# USB_PowerOnly.net
KiCad netlist of a schematic drawn in Altium Designer
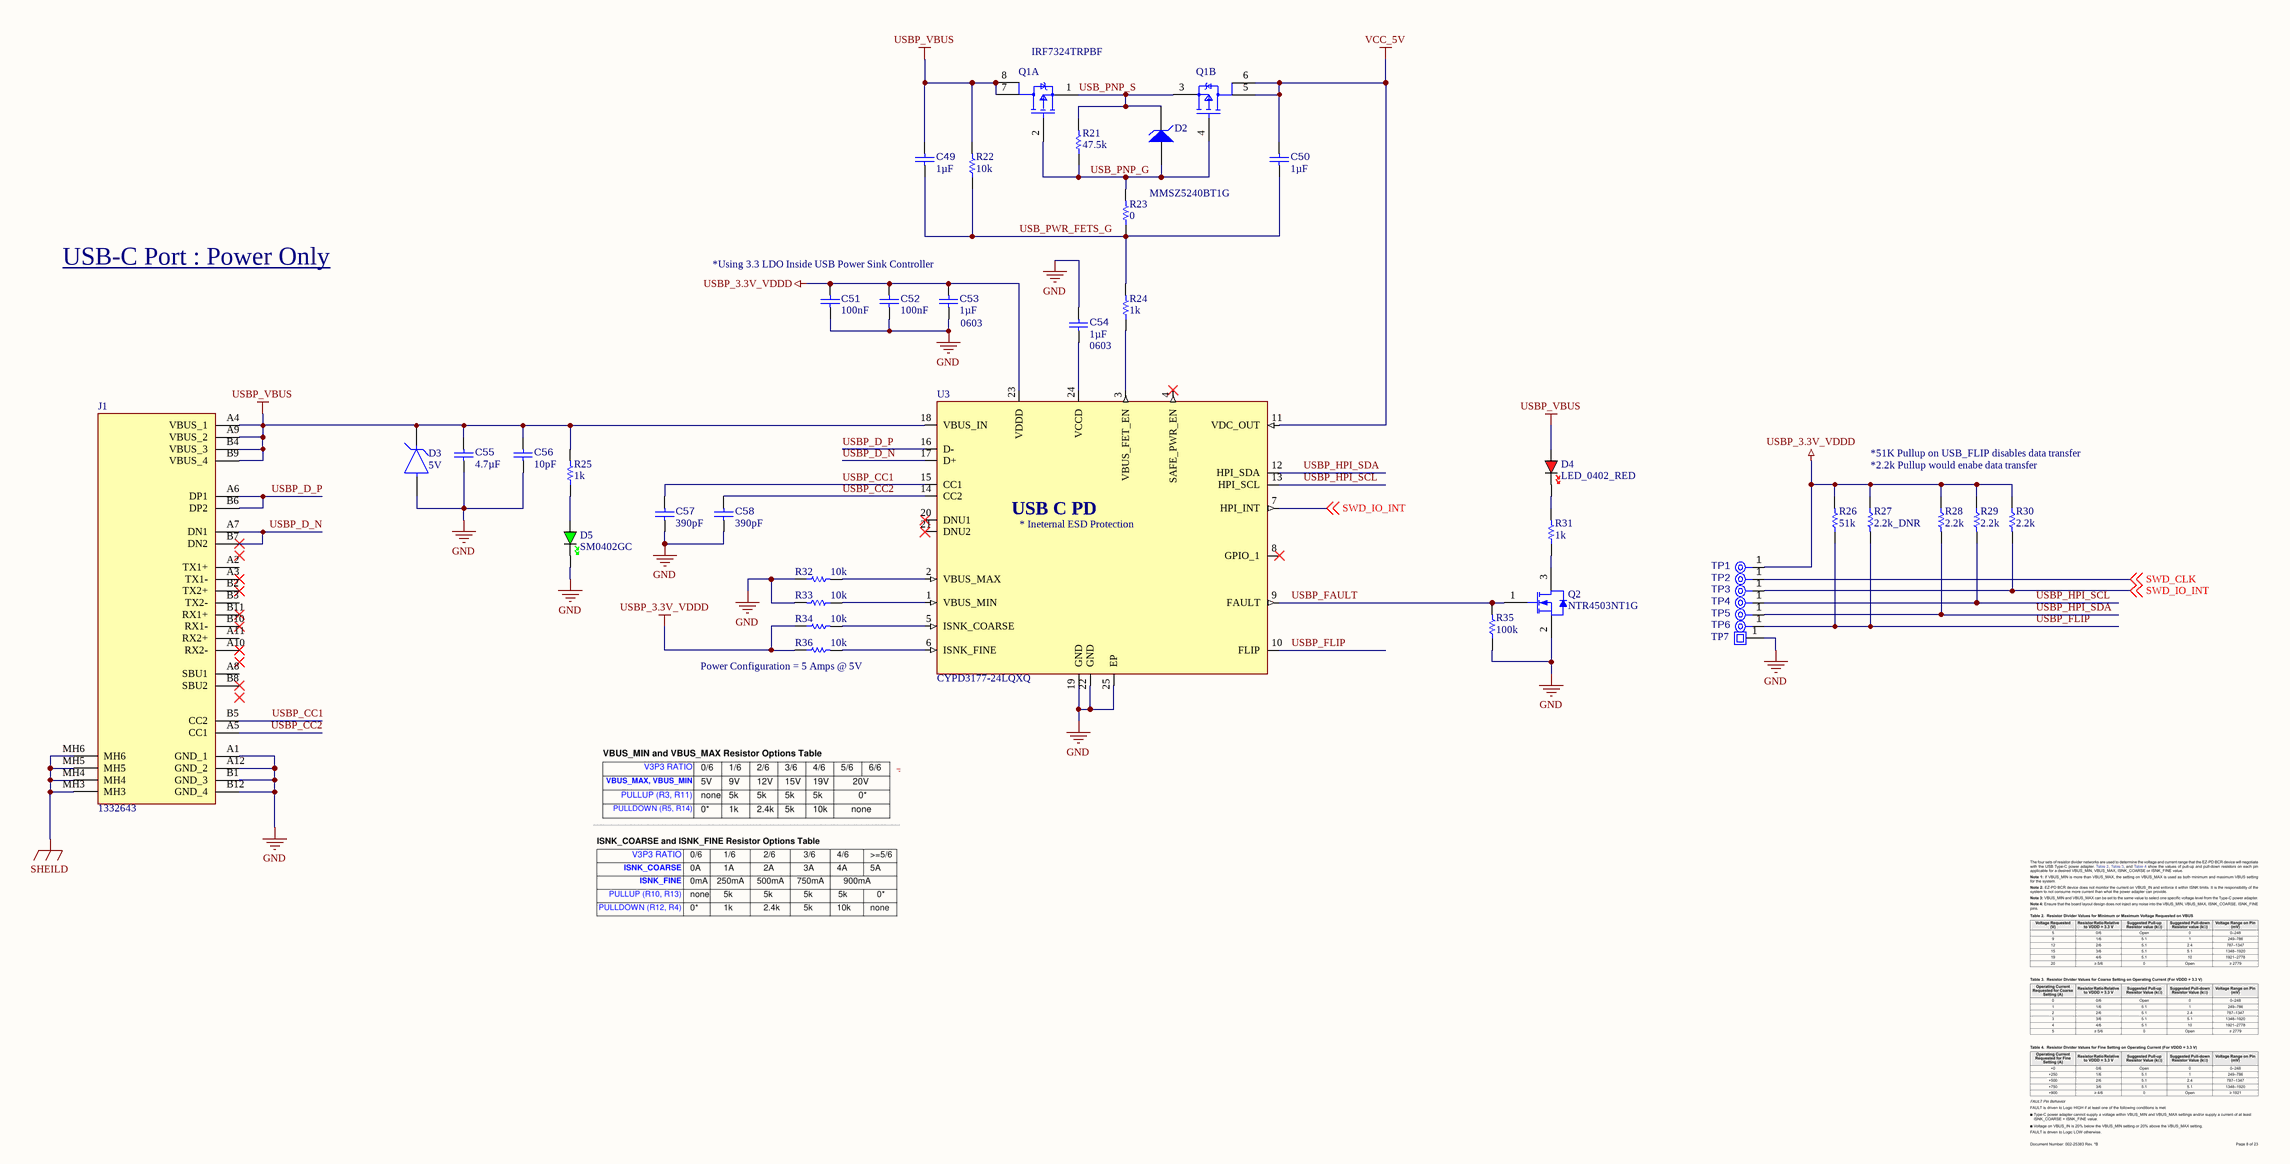
[diagram p0: USB_PowerOnly.SchDoc]

(export (version "E")
  (design (tool "Eeschema 10.0.6"))
  (components
    (comp (ref "C49")
      (value "1µF")
      (footprint "CAPC2013X135X45NL10T25")
      (description "Chip Capacitor, 1 uF, +/- 10%, 50 V, 0805 (2012 Metric)")
      (fields (field (name "TOLERANCE") "10%") (field (name "Comment") "Capacitor 1 uF +/- 10% 50 V 0805"))
      (libsource (lib "Personal Workspace") (part "CAP-NP-2"))
    )
    (comp (ref "C50")
      (value "1µF")
      (footprint "CAPC2013X135X45NL10T25")
      (description "Chip Capacitor, 1 uF, +/- 10%, 50 V, 0805 (2012 Metric)")
      (fields (field (name "TOLERANCE") "10%") (field (name "Comment") "Capacitor 1 uF +/- 10% 50 V 0805"))
      (libsource (lib "Personal Workspace") (part "CAP-NP-2"))
    )
    (comp (ref "C51")
      (value "100nF")
      (footprint "CAPC2013X145X48ML20T23")
      (fields (field (name "Comment") "VJ0805Y104JXXAT"))
      (libsource (lib "Personal Workspace") (part "CAP-NP-2"))
    )
    (comp (ref "C52")
      (value "100nF")
      (footprint "CAPC2013X145X48ML20T23")
      (fields (field (name "Comment") "VJ0805Y104JXXAT"))
      (libsource (lib "Personal Workspace") (part "CAP-NP-2"))
    )
    (comp (ref "C53")
      (value "1µF")
      (footprint "CAPC1608X90X35LL15T15")
      (description "0603 1 uF 16 V ±5 % Tolerance X7R Surface Mount Multilayer Ceramic Capacitor")
      (fields
        (field (name "TOLERANCE") "5%")
        (field (name "CASE/PACKAGE") "0603")
        (field (name "Comment") "0603YC105JAT2A")
      )
      (libsource (lib "Personal Workspace") (part "CAP-NP-2"))
    )
    (comp (ref "C54")
      (value "1µF")
      (footprint "CAPC1608X90X35LL15T15")
      (description "0603 1 uF 16 V ±5 % Tolerance X7R Surface Mount Multilayer Ceramic Capacitor")
      (fields
        (field (name "TOLERANCE") "5%")
        (field (name "CASE/PACKAGE") "0603")
        (field (name "Comment") "0603YC105JAT2A")
      )
      (libsource (lib "Personal Workspace") (part "CAP-NP-2"))
    )
    (comp (ref "C55")
      (value "4.7µF")
      (footprint "CAPC0805(2012)145_L")
      (description "Chip Capacitor, 4.7µF +/-40%, 25V, 0805, Thickness 1.45 mm")
      (fields (field (name "TOLERANCE") "20%") (field (name "Comment") "Capacitor 4.7µF +/-40% 25V 0805"))
      (libsource (lib "Personal Workspace") (part "CAP-NP-2"))
    )
    (comp (ref "C56")
      (value "10pF")
      (footprint "CAPC1005X55X25ML05T05")
      (description "Chip Capacitor, 10 pF, +/- 5%, 50 V, 0402 (1005 Metric)")
      (fields (field (name "TOLERANCE") "5%") (field (name "Comment") "Capacitor 10 pF +/- 5% 50 V 0402"))
      (libsource (lib "Personal Workspace") (part "CAP-NP-2"))
    )
    (comp (ref "C57")
      (value "390pF")
      (footprint "FP-C0402-BB-MFG")
      (description "Multilayer Ceramic Capacitors MLCC - SMD/SMT 16V 390pF X7R 0402 10%")
      (fields (field (name "TOLERANCE") "10%") (field (name "Comment") "C0402C391K4RACTU"))
      (libsource (lib "Personal Workspace") (part "CAP-NP-2"))
    )
    (comp (ref "C58")
      (value "390pF")
      (footprint "FP-C0402-BB-MFG")
      (description "Multilayer Ceramic Capacitors MLCC - SMD/SMT 16V 390pF X7R 0402 10%")
      (fields (field (name "TOLERANCE") "10%") (field (name "Comment") "C0402C391K4RACTU"))
      (libsource (lib "Personal Workspace") (part "CAP-NP-2"))
    )
    (comp (ref "D2")
      (value "MMSZ5240BT1G")
      (footprint "ONSC-SOD-123-2-425-04_V")
      (description "Zener Voltage Regulator, 500 mW, 2-Pin SOD-123, Pb-Free, Tape and Reel")
      (fields (field (name "MANUFACTURER") "On Semiconductor"))
      (libsource (lib "Altium Content Vault") (part "ONSC-K1A2-2"))
    )
    (comp (ref "D3")
      (value "SMAJ5.0A-13-F")
      (footprint "FP-SMA-MFG")
      (description "TVS DIODE 5V 9.2V SMA")
      (fields
        (field (name "MANUFACTURER") "Diodes Inc.")
        (field (name "OCTOPART") "https://octopart.com/smaj5.0a-13-f-diodes+inc.-350158")
        (field (name "REVERSE STANDOFF VOLTAGE") "5V")
      )
      (libsource (lib "Personal Workspace") (part "SMAJ5.0A-13-F"))
    )
    (comp (ref "D4")
      (value "LED_0402_RED")
      (footprint "LED_0402_RED")
      (description "LED 0402 RED SMD")
      (fields (field (name "SOURCE") "Schematic-Lib-PhilsLab.SchLib"))
      (libsource (lib "Personal Workspace") (part "LED_0603_RED"))
    )
    (comp (ref "D5")
      (value "SM0402GC")
      (footprint "FP-SM0402GC-MFG")
      (description "LED Uni-Color Green 575nm 2-PinChip 0402(1006Metric) T/R")
      (libsource (lib "Personal Workspace") (part "LED_0805_GREEN"))
    )
    (comp (ref "J1")
      (value "1332643")
      (footprint "1332643")
      (description "USB-C connector. Horizontal layout. 5A amp rated.")
      (fields (field (name "MOUSER PART NUMBER") "651-1332643"))
      (libsource (lib "Personal Workspace") (part "1332643"))
    )
    (comp (ref "Q1")
      (value "IRF7324TRPBF")
      (footprint "FP-PG-DSO-8-IPC_B")
      (description "MOSFET 2P-CH 20V 9A 8-SOIC")
      (libsource (lib "Altium Content Vault") (part "3b34c718ba17fc0ccb4bdecb033d164"))
    )
    (comp (ref "Q2")
      (value "NTR4503NT1G")
      (footprint "ONSC-SOT-23-3-318-08_V")
      (description "Power MOSFET, 30 V, 2.5 A, Single N-Channel, 3-Pin SOT-23, Pb-Free, Tape and Reel")
      (fields (field (name "MANUFACTURER") "On Semiconductor"))
      (libsource (lib "Altium Content Vault") (part "ONSC-NMOS-G1S2D3-3"))
    )
    (comp (ref "R21")
      (value "47.5k")
      (footprint "RESC0402(1005)_L")
      (description "Chip Resistor, 47,5 kOhms, +/-1 %, 63 mW, -55 to 155 degC, 0402")
      (fields (field (name "TOLERANCE") "1%") (field (name "POWER") "63mW"))
      (libsource (lib "Personal Workspace") (part "RES-2"))
    )
    (comp (ref "R22")
      (value "10k")
      (footprint "RESC1005X40X25ML05T05")
      (description "Chip Resistor, 10 KOhm, +/- 1%, 0.1 W, -55 to 155 degC, 0402 (1005 Metric)")
      (fields (field (name "TOLERANCE") "1%") (field (name "POWER") "100mW"))
      (libsource (lib "Personal Workspace") (part "RES-2"))
    )
    (comp (ref "R23")
      (value "0")
      (footprint "RESC1005X40X25ML05T05")
      (description "Chip Resistor, 0 Ohm, 0.1 W, -55 to 155 degC, 0402 (1005 Metric)")
      (fields (field (name "TOLERANCE") "5%") (field (name "POWER") "100mW"))
      (libsource (lib "Personal Workspace") (part "RES-2"))
    )
    (comp (ref "R24")
      (value "1k")
      (footprint "RESC0402(1005)_L")
      (description "Chip Resistor, 1 kOhms, +/-5 %, 63 mW, -55 to 155 degC, 0402")
      (fields (field (name "TOLERANCE") "5%") (field (name "POWER") "63mW"))
      (libsource (lib "Personal Workspace") (part "RES-2"))
    )
    (comp (ref "R25")
      (value "1k")
      (footprint "RESC0402(1005)_L")
      (description "Chip Resistor, 1 kOhms, +/-5 %, 63 mW, -55 to 155 degC, 0402")
      (fields (field (name "TOLERANCE") "5%") (field (name "POWER") "63mW"))
      (libsource (lib "Personal Workspace") (part "RES-2"))
    )
    (comp (ref "R26")
      (value "51k")
      (footprint "RESC1005X40X25ML05T10")
      (description "Chip Resistor, 51 KOhm, +/- 5%, 0.063 W, -55 to 155 degC, 0402 (1005 Metric)")
      (fields (field (name "TOLERANCE") "5%") (field (name "POWER") "63mW"))
      (libsource (lib "Personal Workspace") (part "RES-2"))
    )
    (comp (ref "R27")
      (value "2.2k_DNR")
      (footprint "RESC0402(1005)_L")
      (description "Chip Resistor, 2,2 kOhms, +/-5 %, 63 mW, -55 to 155 degC, 0402")
      (fields (field (name "POWER") "63mW") (field (name "TOLERANCE") "5%"))
      (libsource (lib "Personal Workspace") (part "RES-2"))
    )
    (comp (ref "R28")
      (value "2.2k")
      (footprint "RESC0402(1005)_L")
      (description "Chip Resistor, 2,2 kOhms, +/-5 %, 63 mW, -55 to 155 degC, 0402")
      (fields (field (name "POWER") "63mW") (field (name "TOLERANCE") "5%"))
      (libsource (lib "Personal Workspace") (part "RES-2"))
    )
    (comp (ref "R29")
      (value "2.2k")
      (footprint "RESC0402(1005)_L")
      (description "Chip Resistor, 2,2 kOhms, +/-5 %, 63 mW, -55 to 155 degC, 0402")
      (fields (field (name "POWER") "63mW") (field (name "TOLERANCE") "5%"))
      (libsource (lib "Personal Workspace") (part "RES-2"))
    )
    (comp (ref "R30")
      (value "2.2k")
      (footprint "RESC0402(1005)_L")
      (description "Chip Resistor, 2,2 kOhms, +/-5 %, 63 mW, -55 to 155 degC, 0402")
      (fields (field (name "POWER") "63mW") (field (name "TOLERANCE") "5%"))
      (libsource (lib "Personal Workspace") (part "RES-2"))
    )
    (comp (ref "R31")
      (value "1k")
      (footprint "RESC0402(1005)_L")
      (description "Chip Resistor, 1 kOhms, +/-5 %, 63 mW, -55 to 155 degC, 0402")
      (fields (field (name "TOLERANCE") "5%") (field (name "POWER") "63mW"))
      (libsource (lib "Personal Workspace") (part "RES-2"))
    )
    (comp (ref "R32")
      (value "10k")
      (footprint "RESC1005X40X25ML05T05")
      (description "Chip Resistor, 10 KOhm, +/- 1%, 0.1 W, -55 to 155 degC, 0402 (1005 Metric)")
      (fields (field (name "TOLERANCE") "1%") (field (name "POWER") "100mW"))
      (libsource (lib "Personal Workspace") (part "RES-2"))
    )
    (comp (ref "R33")
      (value "10k")
      (footprint "RESC1005X40X25ML05T05")
      (description "Chip Resistor, 10 KOhm, +/- 1%, 0.1 W, -55 to 155 degC, 0402 (1005 Metric)")
      (fields (field (name "TOLERANCE") "1%") (field (name "POWER") "100mW"))
      (libsource (lib "Personal Workspace") (part "RES-2"))
    )
    (comp (ref "R34")
      (value "10k")
      (footprint "RESC1005X40X25ML05T05")
      (description "Chip Resistor, 10 KOhm, +/- 1%, 0.1 W, -55 to 155 degC, 0402 (1005 Metric)")
      (fields (field (name "TOLERANCE") "1%") (field (name "POWER") "100mW"))
      (libsource (lib "Personal Workspace") (part "RES-2"))
    )
    (comp (ref "R35")
      (value "100k")
      (footprint "RESC1005X40X25ML05T05")
      (description "Chip Resistor, 100 KOhm, +/- 1%, 0.063 W, -55 to 155 degC, 0402 (1005 Metric)")
      (fields (field (name "POWER") "63mW") (field (name "TOLERANCE") "1%"))
      (libsource (lib "Personal Workspace") (part "RES-2"))
    )
    (comp (ref "R36")
      (value "10k")
      (footprint "RESC1005X40X25ML05T05")
      (description "Chip Resistor, 10 KOhm, +/- 1%, 0.1 W, -55 to 155 degC, 0402 (1005 Metric)")
      (fields (field (name "TOLERANCE") "1%") (field (name "POWER") "100mW"))
      (libsource (lib "Personal Workspace") (part "RES-2"))
    )
    (comp (ref "TP1")
      (value "TPAD6R")
      (footprint "TP06R")
      (description "0.6mm round")
      (libsource (lib "Personal Workspace") (part "CMP-001-0001-4"))
    )
    (comp (ref "TP2")
      (value "TPAD6R")
      (footprint "TP06R")
      (description "0.6mm round")
      (libsource (lib "Personal Workspace") (part "CMP-001-0001-4"))
    )
    (comp (ref "TP3")
      (value "TPAD6R")
      (footprint "TP06R")
      (description "0.6mm round")
      (libsource (lib "Personal Workspace") (part "CMP-001-0001-4"))
    )
    (comp (ref "TP4")
      (value "TPAD6R")
      (footprint "TP06R")
      (description "0.6mm round")
      (libsource (lib "Personal Workspace") (part "CMP-001-0001-4"))
    )
    (comp (ref "TP5")
      (value "TPAD6R")
      (footprint "TP06R")
      (description "0.6mm round")
      (libsource (lib "Personal Workspace") (part "CMP-001-0001-4"))
    )
    (comp (ref "TP6")
      (value "TPAD6R")
      (footprint "TP06R")
      (description "0.6mm round")
      (libsource (lib "Personal Workspace") (part "CMP-001-0001-4"))
    )
    (comp (ref "TP7")
      (value "TestPoint_Ground_0.6mm")
      (footprint "TestPoint_Ground_0.6mm-Footprint-1")
      (libsource (lib "Personal Workspace") (part "TestPoint_Ground_0.6mm-Symbol-1"))
    )
    (comp (ref "U3")
      (value "CYPD3177-24LQXQ")
      (footprint "QFN-24-0MM5")
      (description "USB Type-C Port Controller for Power Sinks")
      (fields (field (name "MANUFACTURER") "Cypress Semicon"))
      (libsource (lib "Personal Workspace") (part "CYPD3177-24LQXQ"))
    )
  )
  (nets
    (net (code "1") (name "/USBP_CC1") (class "Default")
      (node (ref "C57") (pin "2") (pinfunction "2_2") (pintype "passive"))
      (node (ref "J1") (pin "B5") (pinfunction "CC2_B5") (pintype "passive"))
      (node (ref "U3") (pin "15") (pinfunction "CC1_15") (pintype "bidirectional"))
    )
    (net (code "2") (name "/USBP_CC2") (class "Default")
      (node (ref "C58") (pin "2") (pinfunction "2_2") (pintype "passive"))
      (node (ref "J1") (pin "A5") (pinfunction "CC1_A5") (pintype "passive"))
      (node (ref "U3") (pin "14") (pinfunction "CC2_14") (pintype "bidirectional"))
    )
    (net (code "3") (name "/USBP_D_N") (class "Default")
      (node (ref "J1") (pin "A7") (pinfunction "DN1_A7") (pintype "passive"))
      (node (ref "J1") (pin "B7") (pinfunction "DN2_B7") (pintype "passive"))
      (node (ref "U3") (pin "17") (pinfunction "D+_17") (pintype "passive"))
    )
    (net (code "4") (name "/USBP_D_P") (class "Default")
      (node (ref "J1") (pin "A6") (pinfunction "DP1_A6") (pintype "passive"))
      (node (ref "J1") (pin "B6") (pinfunction "DP2_B6") (pintype "passive"))
      (node (ref "U3") (pin "16") (pinfunction "D-_16") (pintype "passive"))
    )
    (net (code "5") (name "/USBP_FAULT") (class "Default")
      (node (ref "Q2") (pin "1") (pinfunction "G_1") (pintype "passive"))
      (node (ref "R35") (pin "2") (pinfunction "2_2") (pintype "passive"))
      (node (ref "U3") (pin "9") (pinfunction "FAULT_9") (pintype "output"))
    )
    (net (code "6") (name "/USBP_FLIP") (class "Default")
      (node (ref "R26") (pin "1") (pinfunction "1_1") (pintype "passive"))
      (node (ref "R27") (pin "2") (pinfunction "2_2") (pintype "passive"))
      (node (ref "TP6") (pin "1") (pinfunction "TP_1") (pintype "passive"))
      (node (ref "U3") (pin "10") (pinfunction "FLIP_10") (pintype "open_collector"))
    )
    (net (code "7") (name "/USBP_HPI_SCL") (class "Default")
      (node (ref "R29") (pin "2") (pinfunction "2_2") (pintype "passive"))
      (node (ref "TP4") (pin "1") (pinfunction "TP_1") (pintype "passive"))
      (node (ref "U3") (pin "13") (pinfunction "HPI_SCL_13") (pintype "open_collector"))
    )
    (net (code "8") (name "/USBP_HPI_SDA") (class "Default")
      (node (ref "R28") (pin "2") (pinfunction "2_2") (pintype "passive"))
      (node (ref "TP5") (pin "1") (pinfunction "TP_1") (pintype "passive"))
      (node (ref "U3") (pin "12") (pinfunction "HPI_SDA_12") (pintype "open_collector"))
    )
    (net (code "9") (name "/USB_PNP_G") (class "Default")
      (node (ref "D2") (pin "2") (pinfunction "A_2") (pintype "passive"))
      (node (ref "Q1") (pin "2") (pinfunction "G1_2") (pintype "passive"))
      (node (ref "Q1") (pin "4") (pinfunction "G2_4") (pintype "passive"))
      (node (ref "R21") (pin "1") (pinfunction "1_1") (pintype "passive"))
      (node (ref "R23") (pin "2") (pinfunction "2_2") (pintype "passive"))
    )
    (net (code "10") (name "/USB_PNP_S") (class "Default")
      (node (ref "D2") (pin "1") (pinfunction "K_1") (pintype "passive"))
      (node (ref "Q1") (pin "1") (pinfunction "S1_1") (pintype "passive"))
      (node (ref "Q1") (pin "3") (pinfunction "S2_3") (pintype "passive"))
      (node (ref "R21") (pin "2") (pinfunction "2_2") (pintype "passive"))
    )
    (net (code "11") (name "/USB_PWR_FETS_G") (class "Default")
      (node (ref "C49") (pin "1") (pinfunction "1_1") (pintype "passive"))
      (node (ref "C50") (pin "1") (pinfunction "1_1") (pintype "passive"))
      (node (ref "R22") (pin "1") (pinfunction "1_1") (pintype "passive"))
      (node (ref "R23") (pin "1") (pinfunction "1_1") (pintype "passive"))
      (node (ref "R24") (pin "2") (pinfunction "2_2") (pintype "passive"))
    )
    (net (code "12") (name "GND") (class "Default")
      (node (ref "C51") (pin "1") (pinfunction "1_1") (pintype "passive"))
      (node (ref "C52") (pin "1") (pinfunction "1_1") (pintype "passive"))
      (node (ref "C53") (pin "1") (pinfunction "1_1") (pintype "passive"))
      (node (ref "C54") (pin "1") (pinfunction "1_1") (pintype "passive"))
      (node (ref "C55") (pin "1") (pinfunction "1_1") (pintype "passive"))
      (node (ref "C56") (pin "1") (pinfunction "1_1") (pintype "passive"))
      (node (ref "C57") (pin "1") (pinfunction "1_1") (pintype "passive"))
      (node (ref "C58") (pin "1") (pinfunction "1_1") (pintype "passive"))
      (node (ref "D3") (pin "2") (pinfunction "A_2") (pintype "passive"))
      (node (ref "D5") (pin "K") (pinfunction "K_K") (pintype "passive"))
      (node (ref "J1") (pin "A1") (pinfunction "GND_1_A1") (pintype "passive"))
      (node (ref "J1") (pin "A12") (pinfunction "GND_2_A12") (pintype "passive"))
      (node (ref "J1") (pin "B1") (pinfunction "GND_3_B1") (pintype "passive"))
      (node (ref "J1") (pin "B12") (pinfunction "GND_4_B12") (pintype "passive"))
      (node (ref "Q2") (pin "2") (pinfunction "S_2") (pintype "passive"))
      (node (ref "R32") (pin "1") (pinfunction "1_1") (pintype "passive"))
      (node (ref "R33") (pin "2") (pinfunction "2_2") (pintype "passive"))
      (node (ref "R35") (pin "1") (pinfunction "1_1") (pintype "passive"))
      (node (ref "U3") (pin "19") (pinfunction "GND_19") (pintype "power_in"))
      (node (ref "U3") (pin "22") (pinfunction "GND_22") (pintype "power_in"))
      (node (ref "U3") (pin "25") (pinfunction "EP_25") (pintype "power_in"))
    )
    (net (code "13") (name "Net-(D4-PadK)") (class "Default")
      (node (ref "D4") (pin "K") (pinfunction "K_K") (pintype "passive"))
      (node (ref "R31") (pin "2") (pinfunction "2_2") (pintype "passive"))
    )
    (net (code "14") (name "Net-(D5-PadA)") (class "Default")
      (node (ref "D5") (pin "A") (pinfunction "A_A") (pintype "passive"))
      (node (ref "R25") (pin "1") (pinfunction "1_1") (pintype "passive"))
    )
    (net (code "15") (name "Net-(Q2-D)") (class "Default")
      (node (ref "Q2") (pin "3") (pinfunction "D_3") (pintype "passive"))
      (node (ref "R31") (pin "1") (pinfunction "1_1") (pintype "passive"))
    )
    (net (code "16") (name "Net-(U3-ISNK_COARSE)") (class "Default")
      (node (ref "R34") (pin "2") (pinfunction "2_2") (pintype "passive"))
      (node (ref "U3") (pin "5") (pinfunction "ISNK_COARSE_5") (pintype "input"))
    )
    (net (code "17") (name "Net-(U3-ISNK_FINE)") (class "Default")
      (node (ref "R36") (pin "2") (pinfunction "2_2") (pintype "passive"))
      (node (ref "U3") (pin "6") (pinfunction "ISNK_FINE_6") (pintype "input"))
    )
    (net (code "18") (name "Net-(U3-VBUS_FET_EN)") (class "Default")
      (node (ref "R24") (pin "1") (pinfunction "1_1") (pintype "passive"))
      (node (ref "U3") (pin "3") (pinfunction "VBUS_FET_EN_3") (pintype "output"))
    )
    (net (code "19") (name "Net-(U3-VBUS_MAX)") (class "Default")
      (node (ref "R32") (pin "2") (pinfunction "2_2") (pintype "passive"))
      (node (ref "U3") (pin "2") (pinfunction "VBUS_MAX_2") (pintype "input"))
    )
    (net (code "20") (name "Net-(U3-VBUS_MIN)") (class "Default")
      (node (ref "R33") (pin "1") (pinfunction "1_1") (pintype "passive"))
      (node (ref "U3") (pin "1") (pinfunction "VBUS_MIN_1") (pintype "input"))
    )
    (net (code "21") (name "Net-(U3-VCCD)") (class "Default")
      (node (ref "C54") (pin "2") (pinfunction "2_2") (pintype "passive"))
      (node (ref "U3") (pin "24") (pinfunction "VCCD_24") (pintype "power_in"))
    )
    (net (code "22") (name "SHEILD") (class "Default")
      (node (ref "J1") (pin "MH3") (pinfunction "MH3_MH3") (pintype "passive"))
      (node (ref "J1") (pin "MH4") (pinfunction "MH4_MH4") (pintype "passive"))
      (node (ref "J1") (pin "MH5") (pinfunction "MH5_MH5") (pintype "passive"))
      (node (ref "J1") (pin "MH6") (pinfunction "MH6_MH6") (pintype "passive"))
    )
    (net (code "23") (name "SWD_CLK") (class "Default")
      (node (ref "TP2") (pin "1") (pinfunction "TP_1") (pintype "passive"))
    )
    (net (code "24") (name "SWD_IO_INT") (class "Default")
      (node (ref "R30") (pin "2") (pinfunction "2_2") (pintype "passive"))
      (node (ref "TP3") (pin "1") (pinfunction "TP_1") (pintype "passive"))
      (node (ref "U3") (pin "7") (pinfunction "HPI_INT_7") (pintype "output"))
    )
    (net (code "25") (name "USBP_3.3V_VDDD") (class "Default")
      (node (ref "C51") (pin "2") (pinfunction "2_2") (pintype "passive"))
      (node (ref "C52") (pin "2") (pinfunction "2_2") (pintype "passive"))
      (node (ref "C53") (pin "2") (pinfunction "2_2") (pintype "passive"))
      (node (ref "R26") (pin "2") (pinfunction "2_2") (pintype "passive"))
      (node (ref "R27") (pin "1") (pinfunction "1_1") (pintype "passive"))
      (node (ref "R28") (pin "1") (pinfunction "1_1") (pintype "passive"))
      (node (ref "R29") (pin "1") (pinfunction "1_1") (pintype "passive"))
      (node (ref "R30") (pin "1") (pinfunction "1_1") (pintype "passive"))
      (node (ref "R34") (pin "1") (pinfunction "1_1") (pintype "passive"))
      (node (ref "R36") (pin "1") (pinfunction "1_1") (pintype "passive"))
      (node (ref "TP1") (pin "1") (pinfunction "TP_1") (pintype "passive"))
      (node (ref "U3") (pin "23") (pinfunction "VDDD_23") (pintype "power_in"))
    )
    (net (code "26") (name "USBP_VBUS") (class "Default")
      (node (ref "C49") (pin "2") (pinfunction "2_2") (pintype "passive"))
      (node (ref "C55") (pin "2") (pinfunction "2_2") (pintype "passive"))
      (node (ref "C56") (pin "2") (pinfunction "2_2") (pintype "passive"))
      (node (ref "D3") (pin "1") (pinfunction "C_1") (pintype "passive"))
      (node (ref "D4") (pin "A") (pinfunction "A_A") (pintype "passive"))
      (node (ref "J1") (pin "A4") (pinfunction "VBUS_1_A4") (pintype "passive"))
      (node (ref "J1") (pin "A9") (pinfunction "VBUS_2_A9") (pintype "passive"))
      (node (ref "J1") (pin "B4") (pinfunction "VBUS_3_B4") (pintype "passive"))
      (node (ref "J1") (pin "B9") (pinfunction "VBUS_4_B9") (pintype "passive"))
      (node (ref "Q1") (pin "7") (pinfunction "D1_7") (pintype "passive"))
      (node (ref "Q1") (pin "8") (pinfunction "D1_8") (pintype "passive"))
      (node (ref "R22") (pin "2") (pinfunction "2_2") (pintype "passive"))
      (node (ref "R25") (pin "2") (pinfunction "2_2") (pintype "passive"))
      (node (ref "U3") (pin "18") (pinfunction "VBUS_IN_18") (pintype "power_in"))
    )
    (net (code "27") (name "VCC_5V") (class "Default")
      (node (ref "C50") (pin "2") (pinfunction "2_2") (pintype "passive"))
      (node (ref "Q1") (pin "5") (pinfunction "D2_5") (pintype "passive"))
      (node (ref "Q1") (pin "6") (pinfunction "D2_6") (pintype "passive"))
      (node (ref "U3") (pin "11") (pinfunction "VDC_OUT_11") (pintype "input"))
    )
    (net (code "28") (name "unconnected-(J1-RX1+-PadB11)") (class "Default")
      (node (ref "J1") (pin "B11") (pinfunction "RX1+_B11") (pintype "passive+no_connect"))
    )
    (net (code "29") (name "unconnected-(J1-RX1--PadB10)") (class "Default")
      (node (ref "J1") (pin "B10") (pinfunction "RX1-_B10") (pintype "passive+no_connect"))
    )
    (net (code "30") (name "unconnected-(J1-RX2+-PadA11)") (class "Default")
      (node (ref "J1") (pin "A11") (pinfunction "RX2+_A11") (pintype "passive"))
    )
    (net (code "31") (name "unconnected-(J1-RX2--PadA10)") (class "Default")
      (node (ref "J1") (pin "A10") (pinfunction "RX2-_A10") (pintype "passive+no_connect"))
    )
    (net (code "32") (name "unconnected-(J1-SBU1-PadA8)") (class "Default")
      (node (ref "J1") (pin "A8") (pinfunction "SBU1_A8") (pintype "passive"))
    )
    (net (code "33") (name "unconnected-(J1-SBU2-PadB8)") (class "Default")
      (node (ref "J1") (pin "B8") (pinfunction "SBU2_B8") (pintype "passive+no_connect"))
    )
    (net (code "34") (name "unconnected-(J1-TX1+-PadA2)") (class "Default")
      (node (ref "J1") (pin "A2") (pinfunction "TX1+_A2") (pintype "passive"))
    )
    (net (code "35") (name "unconnected-(J1-TX1--PadA3)") (class "Default")
      (node (ref "J1") (pin "A3") (pinfunction "TX1-_A3") (pintype "passive+no_connect"))
    )
    (net (code "36") (name "unconnected-(J1-TX2+-PadB2)") (class "Default")
      (node (ref "J1") (pin "B2") (pinfunction "TX2+_B2") (pintype "passive+no_connect"))
    )
    (net (code "37") (name "unconnected-(J1-TX2--PadB3)") (class "Default")
      (node (ref "J1") (pin "B3") (pinfunction "TX2-_B3") (pintype "passive"))
    )
    (net (code "38") (name "unconnected-(TP7-Pad1)") (class "Default")
      (node (ref "TP7") (pin "1") (pinfunction "1_1") (pintype "passive"))
    )
    (net (code "39") (name "unconnected-(U3-DNU1-Pad20)") (class "Default")
      (node (ref "U3") (pin "20") (pinfunction "DNU1_20") (pintype "passive+no_connect"))
    )
    (net (code "40") (name "unconnected-(U3-DNU2-Pad21)") (class "Default")
      (node (ref "U3") (pin "21") (pinfunction "DNU2_21") (pintype "passive+no_connect"))
    )
    (net (code "41") (name "unconnected-(U3-GPIO_1-Pad8)") (class "Default")
      (node (ref "U3") (pin "8") (pinfunction "GPIO_1_8") (pintype "bidirectional+no_connect"))
    )
    (net (code "42") (name "unconnected-(U3-SAFE_PWR_EN-Pad4)") (class "Default")
      (node (ref "U3") (pin "4") (pinfunction "SAFE_PWR_EN_4") (pintype "output+no_connect"))
    )
  )
)
